# FlipdotMini.net
KiCad netlist of a schematic drawn in EAGLE
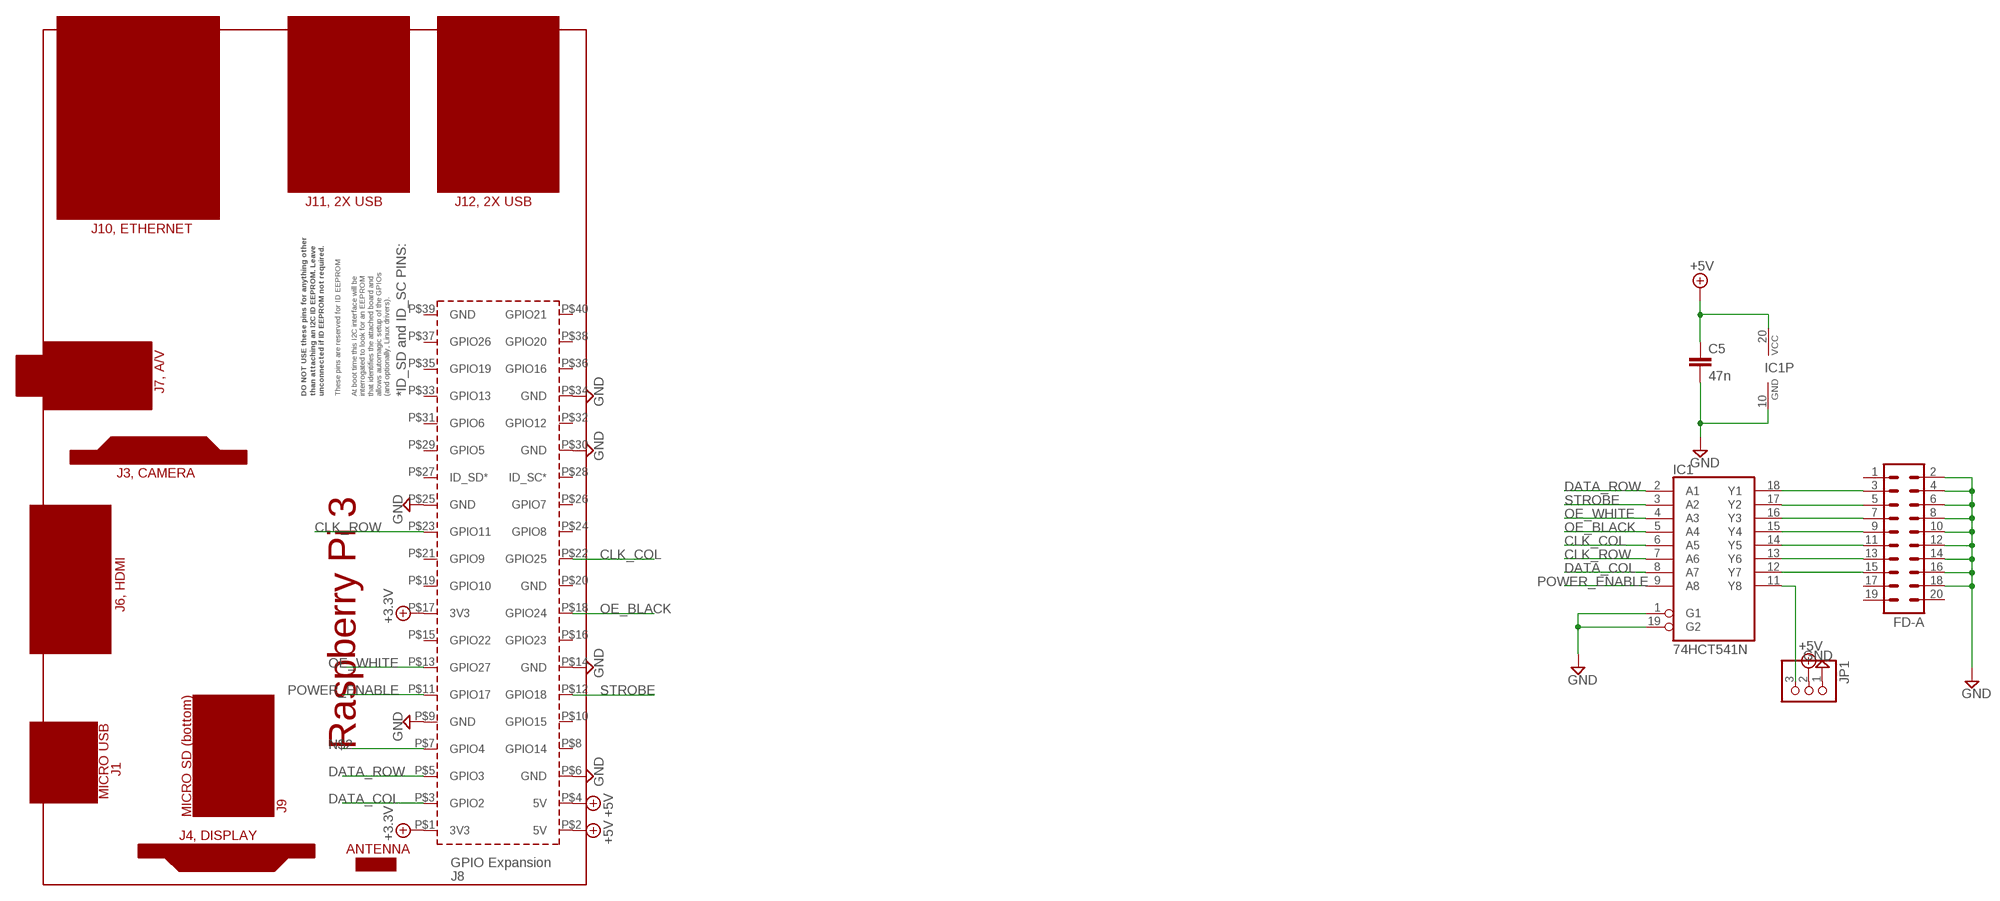
[diagram p0: schematic, sheet 1]

(export (version "E")
  (design (tool "Eeschema 10.0.6"))
  (components
    (comp (ref "C5")
      (value "47n")
      (footprint "eagle-import:C0805")
      (libsource (lib "eagle-import") (part "C-EUC0805"))
    )
    (comp (ref "FD-A")
      (value "MA10-2")
      (footprint "eagle-import:MA10-2")
      (libsource (lib "eagle-import") (part "MA10-2"))
    )
    (comp (ref "IC1")
      (value "74HCT541N")
      (footprint "eagle-import:DIL20")
      (libsource (lib "eagle-import") (part "74541NHCT"))
    )
    (comp (ref "JP1")
      (value "PINHD-1X3")
      (footprint "eagle-import:1X03")
      (libsource (lib "eagle-import") (part "PINHD-1X3"))
    )
    (comp (ref "PCB1")
      (value "RPI3")
      (footprint "eagle-import:RPI3")
      (libsource (lib "eagle-import") (part "RPI3"))
    )
  )
  (nets
    (net (code "1") (name "+3.3V") (class "Default")
      (node (ref "PCB1") (pin "P$1") (pinfunction "3V3_P$1") (pintype "bidirectional"))
      (node (ref "PCB1") (pin "P$17") (pinfunction "3V3_P$17") (pintype "bidirectional"))
    )
    (net (code "2") (name "+5V") (class "Default")
      (node (ref "C5") (pin "1") (pinfunction "1_1") (pintype "passive"))
      (node (ref "IC1") (pin "20") (pinfunction "VCC_20") (pintype "power_in"))
      (node (ref "JP1") (pin "2") (pinfunction "2_2") (pintype "passive"))
      (node (ref "PCB1") (pin "P$2") (pinfunction "5V_P$2") (pintype "bidirectional"))
      (node (ref "PCB1") (pin "P$4") (pinfunction "5V_P$4") (pintype "bidirectional"))
    )
    (net (code "3") (name "/CLK_COL") (class "Default")
      (node (ref "IC1") (pin "6") (pinfunction "A5_6") (pintype "input"))
      (node (ref "PCB1") (pin "P$22") (pinfunction "GPIO25_P$22") (pintype "bidirectional"))
    )
    (net (code "4") (name "/CLK_ROW") (class "Default")
      (node (ref "IC1") (pin "7") (pinfunction "A6_7") (pintype "input"))
      (node (ref "PCB1") (pin "P$23") (pinfunction "GPIO11_P$23") (pintype "bidirectional"))
    )
    (net (code "5") (name "/DATA_COL") (class "Default")
      (node (ref "IC1") (pin "8") (pinfunction "A7_8") (pintype "input"))
      (node (ref "PCB1") (pin "P$3") (pinfunction "GPIO2_P$3") (pintype "bidirectional"))
    )
    (net (code "6") (name "/DATA_ROW") (class "Default")
      (node (ref "IC1") (pin "2") (pinfunction "A1_2") (pintype "input"))
      (node (ref "PCB1") (pin "P$5") (pinfunction "GPIO3_P$5") (pintype "bidirectional"))
    )
    (net (code "7") (name "/N$2") (class "Default")
      (node (ref "PCB1") (pin "P$7") (pinfunction "GPIO4_P$7") (pintype "bidirectional"))
    )
    (net (code "8") (name "/OE_BLACK") (class "Default")
      (node (ref "IC1") (pin "5") (pinfunction "A4_5") (pintype "input"))
      (node (ref "PCB1") (pin "P$18") (pinfunction "GPIO24_P$18") (pintype "bidirectional"))
    )
    (net (code "9") (name "/OE_WHITE") (class "Default")
      (node (ref "IC1") (pin "4") (pinfunction "A3_4") (pintype "input"))
      (node (ref "PCB1") (pin "P$13") (pinfunction "GPIO27_P$13") (pintype "bidirectional"))
    )
    (net (code "10") (name "/POWER_ENABLE") (class "Default")
      (node (ref "IC1") (pin "9") (pinfunction "A8_9") (pintype "input"))
      (node (ref "PCB1") (pin "P$11") (pinfunction "GPIO17_P$11") (pintype "bidirectional"))
    )
    (net (code "11") (name "/STROBE") (class "Default")
      (node (ref "IC1") (pin "3") (pinfunction "A2_3") (pintype "input"))
      (node (ref "PCB1") (pin "P$12") (pinfunction "GPIO18_P$12") (pintype "bidirectional"))
    )
    (net (code "12") (name "GND") (class "Default")
      (node (ref "C5") (pin "2") (pinfunction "2_2") (pintype "passive"))
      (node (ref "FD-A") (pin "10") (pinfunction "10_10") (pintype "passive"))
      (node (ref "FD-A") (pin "12") (pinfunction "12_12") (pintype "passive"))
      (node (ref "FD-A") (pin "14") (pinfunction "14_14") (pintype "passive"))
      (node (ref "FD-A") (pin "16") (pinfunction "16_16") (pintype "passive"))
      (node (ref "FD-A") (pin "18") (pinfunction "18_18") (pintype "passive"))
      (node (ref "FD-A") (pin "2") (pinfunction "2_2") (pintype "passive"))
      (node (ref "FD-A") (pin "4") (pinfunction "4_4") (pintype "passive"))
      (node (ref "FD-A") (pin "6") (pinfunction "6_6") (pintype "passive"))
      (node (ref "FD-A") (pin "8") (pinfunction "8_8") (pintype "passive"))
      (node (ref "IC1") (pin "1") (pinfunction "G1_1") (pintype "input"))
      (node (ref "IC1") (pin "10") (pinfunction "GND_10") (pintype "power_in"))
      (node (ref "IC1") (pin "19") (pinfunction "G2_19") (pintype "input"))
      (node (ref "JP1") (pin "1") (pinfunction "1_1") (pintype "passive"))
      (node (ref "PCB1") (pin "P$14") (pinfunction "GND_P$14") (pintype "bidirectional"))
      (node (ref "PCB1") (pin "P$25") (pinfunction "GND_P$25") (pintype "bidirectional"))
      (node (ref "PCB1") (pin "P$30") (pinfunction "GND_P$30") (pintype "bidirectional"))
      (node (ref "PCB1") (pin "P$34") (pinfunction "GND_P$34") (pintype "bidirectional"))
      (node (ref "PCB1") (pin "P$6") (pinfunction "GND_P$6") (pintype "bidirectional"))
      (node (ref "PCB1") (pin "P$9") (pinfunction "GND_P$9") (pintype "bidirectional"))
    )
    (net (code "13") (name "Net-(IC1A-Y1)") (class "Default")
      (node (ref "FD-A") (pin "3") (pinfunction "3_3") (pintype "passive"))
      (node (ref "IC1") (pin "18") (pinfunction "Y1_18") (pintype "tri_state"))
    )
    (net (code "14") (name "Net-(IC1A-Y2)") (class "Default")
      (node (ref "FD-A") (pin "5") (pinfunction "5_5") (pintype "passive"))
      (node (ref "IC1") (pin "17") (pinfunction "Y2_17") (pintype "tri_state"))
    )
    (net (code "15") (name "Net-(IC1A-Y3)") (class "Default")
      (node (ref "FD-A") (pin "7") (pinfunction "7_7") (pintype "passive"))
      (node (ref "IC1") (pin "16") (pinfunction "Y3_16") (pintype "tri_state"))
    )
    (net (code "16") (name "Net-(IC1A-Y4)") (class "Default")
      (node (ref "FD-A") (pin "9") (pinfunction "9_9") (pintype "passive"))
      (node (ref "IC1") (pin "15") (pinfunction "Y4_15") (pintype "tri_state"))
    )
    (net (code "17") (name "Net-(IC1A-Y5)") (class "Default")
      (node (ref "FD-A") (pin "11") (pinfunction "11_11") (pintype "passive"))
      (node (ref "IC1") (pin "14") (pinfunction "Y5_14") (pintype "tri_state"))
    )
    (net (code "18") (name "Net-(IC1A-Y6)") (class "Default")
      (node (ref "FD-A") (pin "13") (pinfunction "13_13") (pintype "passive"))
      (node (ref "IC1") (pin "13") (pinfunction "Y6_13") (pintype "tri_state"))
    )
    (net (code "19") (name "Net-(IC1A-Y7)") (class "Default")
      (node (ref "FD-A") (pin "15") (pinfunction "15_15") (pintype "passive"))
      (node (ref "IC1") (pin "12") (pinfunction "Y7_12") (pintype "tri_state"))
    )
    (net (code "20") (name "Net-(IC1A-Y8)") (class "Default")
      (node (ref "IC1") (pin "11") (pinfunction "Y8_11") (pintype "tri_state"))
      (node (ref "JP1") (pin "3") (pinfunction "3_3") (pintype "passive"))
    )
    (net (code "21") (name "unconnected-(FD-A-Pad1)") (class "Default")
      (node (ref "FD-A") (pin "1") (pinfunction "1_1") (pintype "passive"))
    )
    (net (code "22") (name "unconnected-(FD-A-Pad17)") (class "Default")
      (node (ref "FD-A") (pin "17") (pinfunction "17_17") (pintype "passive"))
    )
    (net (code "23") (name "unconnected-(FD-A-Pad19)") (class "Default")
      (node (ref "FD-A") (pin "19") (pinfunction "19_19") (pintype "passive"))
    )
    (net (code "24") (name "unconnected-(FD-A-Pad20)") (class "Default")
      (node (ref "FD-A") (pin "20") (pinfunction "20_20") (pintype "passive"))
    )
    (net (code "25") (name "unconnected-(PCB1-GND-PadP$20)") (class "Default")
      (node (ref "PCB1") (pin "P$20") (pinfunction "GND_P$20") (pintype "bidirectional"))
    )
    (net (code "26") (name "unconnected-(PCB1-GND-PadP$39)") (class "Default")
      (node (ref "PCB1") (pin "P$39") (pinfunction "GND_P$39") (pintype "bidirectional"))
    )
    (net (code "27") (name "unconnected-(PCB1-GPIO5-PadP$29)") (class "Default")
      (node (ref "PCB1") (pin "P$29") (pinfunction "GPIO5_P$29") (pintype "bidirectional"))
    )
    (net (code "28") (name "unconnected-(PCB1-GPIO6-PadP$31)") (class "Default")
      (node (ref "PCB1") (pin "P$31") (pinfunction "GPIO6_P$31") (pintype "bidirectional"))
    )
    (net (code "29") (name "unconnected-(PCB1-GPIO7-PadP$26)") (class "Default")
      (node (ref "PCB1") (pin "P$26") (pinfunction "GPIO7_P$26") (pintype "bidirectional"))
    )
    (net (code "30") (name "unconnected-(PCB1-GPIO8-PadP$24)") (class "Default")
      (node (ref "PCB1") (pin "P$24") (pinfunction "GPIO8_P$24") (pintype "bidirectional"))
    )
    (net (code "31") (name "unconnected-(PCB1-GPIO9-PadP$21)") (class "Default")
      (node (ref "PCB1") (pin "P$21") (pinfunction "GPIO9_P$21") (pintype "bidirectional"))
    )
    (net (code "32") (name "unconnected-(PCB1-GPIO10-PadP$19)") (class "Default")
      (node (ref "PCB1") (pin "P$19") (pinfunction "GPIO10_P$19") (pintype "bidirectional"))
    )
    (net (code "33") (name "unconnected-(PCB1-GPIO12-PadP$32)") (class "Default")
      (node (ref "PCB1") (pin "P$32") (pinfunction "GPIO12_P$32") (pintype "bidirectional"))
    )
    (net (code "34") (name "unconnected-(PCB1-GPIO13-PadP$33)") (class "Default")
      (node (ref "PCB1") (pin "P$33") (pinfunction "GPIO13_P$33") (pintype "bidirectional"))
    )
    (net (code "35") (name "unconnected-(PCB1-GPIO14-PadP$8)") (class "Default")
      (node (ref "PCB1") (pin "P$8") (pinfunction "GPIO14_P$8") (pintype "bidirectional"))
    )
    (net (code "36") (name "unconnected-(PCB1-GPIO15-PadP$10)") (class "Default")
      (node (ref "PCB1") (pin "P$10") (pinfunction "GPIO15_P$10") (pintype "bidirectional"))
    )
    (net (code "37") (name "unconnected-(PCB1-GPIO16-PadP$36)") (class "Default")
      (node (ref "PCB1") (pin "P$36") (pinfunction "GPIO16_P$36") (pintype "bidirectional"))
    )
    (net (code "38") (name "unconnected-(PCB1-GPIO19-PadP$35)") (class "Default")
      (node (ref "PCB1") (pin "P$35") (pinfunction "GPIO19_P$35") (pintype "bidirectional"))
    )
    (net (code "39") (name "unconnected-(PCB1-GPIO20-PadP$38)") (class "Default")
      (node (ref "PCB1") (pin "P$38") (pinfunction "GPIO20_P$38") (pintype "bidirectional"))
    )
    (net (code "40") (name "unconnected-(PCB1-GPIO21-PadP$40)") (class "Default")
      (node (ref "PCB1") (pin "P$40") (pinfunction "GPIO21_P$40") (pintype "bidirectional"))
    )
    (net (code "41") (name "unconnected-(PCB1-GPIO22-PadP$15)") (class "Default")
      (node (ref "PCB1") (pin "P$15") (pinfunction "GPIO22_P$15") (pintype "bidirectional"))
    )
    (net (code "42") (name "unconnected-(PCB1-GPIO23-PadP$16)") (class "Default")
      (node (ref "PCB1") (pin "P$16") (pinfunction "GPIO23_P$16") (pintype "bidirectional"))
    )
    (net (code "43") (name "unconnected-(PCB1-GPIO26-PadP$37)") (class "Default")
      (node (ref "PCB1") (pin "P$37") (pinfunction "GPIO26_P$37") (pintype "bidirectional"))
    )
    (net (code "44") (name "unconnected-(PCB1-ID_SC*-PadP$28)") (class "Default")
      (node (ref "PCB1") (pin "P$28") (pinfunction "ID_SC*_P$28") (pintype "bidirectional"))
    )
    (net (code "45") (name "unconnected-(PCB1-ID_SD*-PadP$27)") (class "Default")
      (node (ref "PCB1") (pin "P$27") (pinfunction "ID_SD*_P$27") (pintype "bidirectional"))
    )
  )
)
